# Optocoupler_Bank.net
KiCad netlist of a schematic drawn in Altium Designer
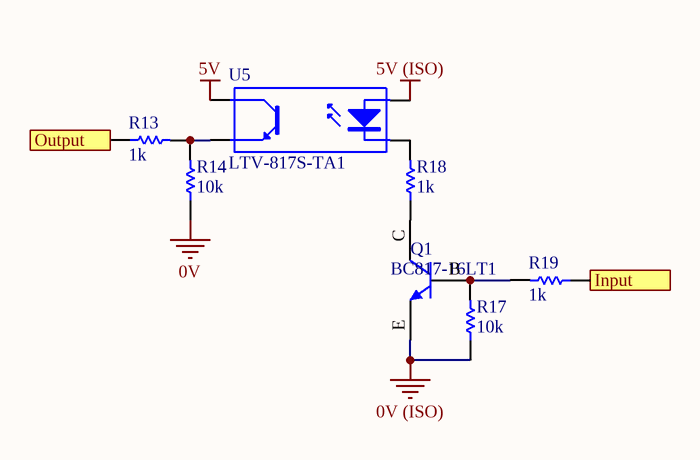
[diagram p0: Optocoupler Bank.SchDoc]

(export (version "E")
  (design (tool "Eeschema 10.0.6"))
  (components
    (comp (ref "Q1")
      (value "BC817-16LT1")
      (footprint "ON SOT-23 BJT")
      (description "300mW  BJT NPN Transistor")
      (fields
        (field (name "MANUFACTURER") "ON Semiconductor")
        (field (name "DIGIKEY PART NUMBER") "BC817-16LT1OSTR-ND")
      )
      (libsource (lib "ts_19-standard-library") (part "NPN"))
    )
    (comp (ref "R13")
      (value "1k")
      (footprint "0805")
      (fields
        (field (name "MANUFACTURER") "YAGEO")
        (field (name "PART NUMBER") "RC0805FR071KL")
        (field (name "TOLERANCE") "0.01")
      )
      (libsource (lib "ts_19-standard-library") (part "Resistor"))
    )
    (comp (ref "R14")
      (value "10k")
      (footprint "0805")
      (fields
        (field (name "MANUFACTURER") "YAGEO")
        (field (name "PART NUMBER") "RC0805FR0710KL")
        (field (name "TOLERANCE") "0.01")
      )
      (libsource (lib "ts_19-standard-library") (part "Resistor"))
    )
    (comp (ref "R17")
      (value "10k")
      (footprint "0805")
      (fields
        (field (name "MANUFACTURER") "YAGEO")
        (field (name "PART NUMBER") "RC0805FR0710KL")
        (field (name "TOLERANCE") "0.01")
      )
      (libsource (lib "ts_19-standard-library") (part "Resistor"))
    )
    (comp (ref "R18")
      (value "1k")
      (footprint "0805")
      (fields
        (field (name "MANUFACTURER") "YAGEO")
        (field (name "PART NUMBER") "RC0805FR071KL")
        (field (name "TOLERANCE") "0.01")
      )
      (libsource (lib "ts_19-standard-library") (part "Resistor"))
    )
    (comp (ref "R19")
      (value "1k")
      (footprint "0805")
      (fields
        (field (name "MANUFACTURER") "YAGEO")
        (field (name "PART NUMBER") "RC0805FR071KL")
        (field (name "TOLERANCE") "0.01")
      )
      (libsource (lib "ts_19-standard-library") (part "Resistor"))
    )
    (comp (ref "U5")
      (value "LTV-817S-TA1")
      (footprint "ON 4-SMD")
      (description "35V 50ma Optocoupler (VF=1.2V)")
      (fields
        (field (name "MANUFACTURER") "Lite-On Inc")
        (field (name "DIGIKEY PART NUMBER") "160-1893-2-ND")
      )
      (libsource (lib "ts_19-standard-library") (part "LTV-817S-TA1"))
    )
  )
  (nets
    (net (code "1") (name "/Input") (class "Default")
      (node (ref "R19") (pin "1") (pinfunction "1_1") (pintype "passive"))
    )
    (net (code "2") (name "/Output") (class "Default")
      (node (ref "R13") (pin "1") (pinfunction "1_1") (pintype "passive"))
    )
    (net (code "3") (name "0V") (class "Default")
      (node (ref "R14") (pin "1") (pinfunction "1_1") (pintype "passive"))
    )
    (net (code "4") (name "0V (ISO)") (class "Default")
      (node (ref "Q1") (pin "E") (pinfunction "E_E") (pintype "passive"))
      (node (ref "R17") (pin "1") (pinfunction "1_1") (pintype "passive"))
    )
    (net (code "5") (name "5V") (class "Default")
      (node (ref "U5") (pin "4") (pinfunction "C_4") (pintype "passive"))
    )
    (net (code "6") (name "5V (ISO)") (class "Default")
      (node (ref "U5") (pin "1") (pinfunction "A_1") (pintype "passive"))
    )
    (net (code "7") (name "Net-(Q1-PadB)") (class "Default")
      (node (ref "Q1") (pin "B") (pinfunction "B_B") (pintype "passive"))
      (node (ref "R17") (pin "2") (pinfunction "2_2") (pintype "passive"))
      (node (ref "R19") (pin "2") (pinfunction "2_2") (pintype "passive"))
    )
    (net (code "8") (name "Net-(Q1-PadC)") (class "Default")
      (node (ref "Q1") (pin "C") (pinfunction "C_C") (pintype "passive"))
      (node (ref "R18") (pin "1") (pinfunction "1_1") (pintype "passive"))
    )
    (net (code "9") (name "Net-(U5-E)") (class "Default")
      (node (ref "R13") (pin "2") (pinfunction "2_2") (pintype "passive"))
      (node (ref "R14") (pin "2") (pinfunction "2_2") (pintype "passive"))
      (node (ref "U5") (pin "3") (pinfunction "E_3") (pintype "passive"))
    )
    (net (code "10") (name "Net-(U5-K)") (class "Default")
      (node (ref "R18") (pin "2") (pinfunction "2_2") (pintype "passive"))
      (node (ref "U5") (pin "2") (pinfunction "K_2") (pintype "passive"))
    )
  )
)
